# USV-BG-001-SP-A.net
KiCad netlist of a schematic drawn in EAGLE
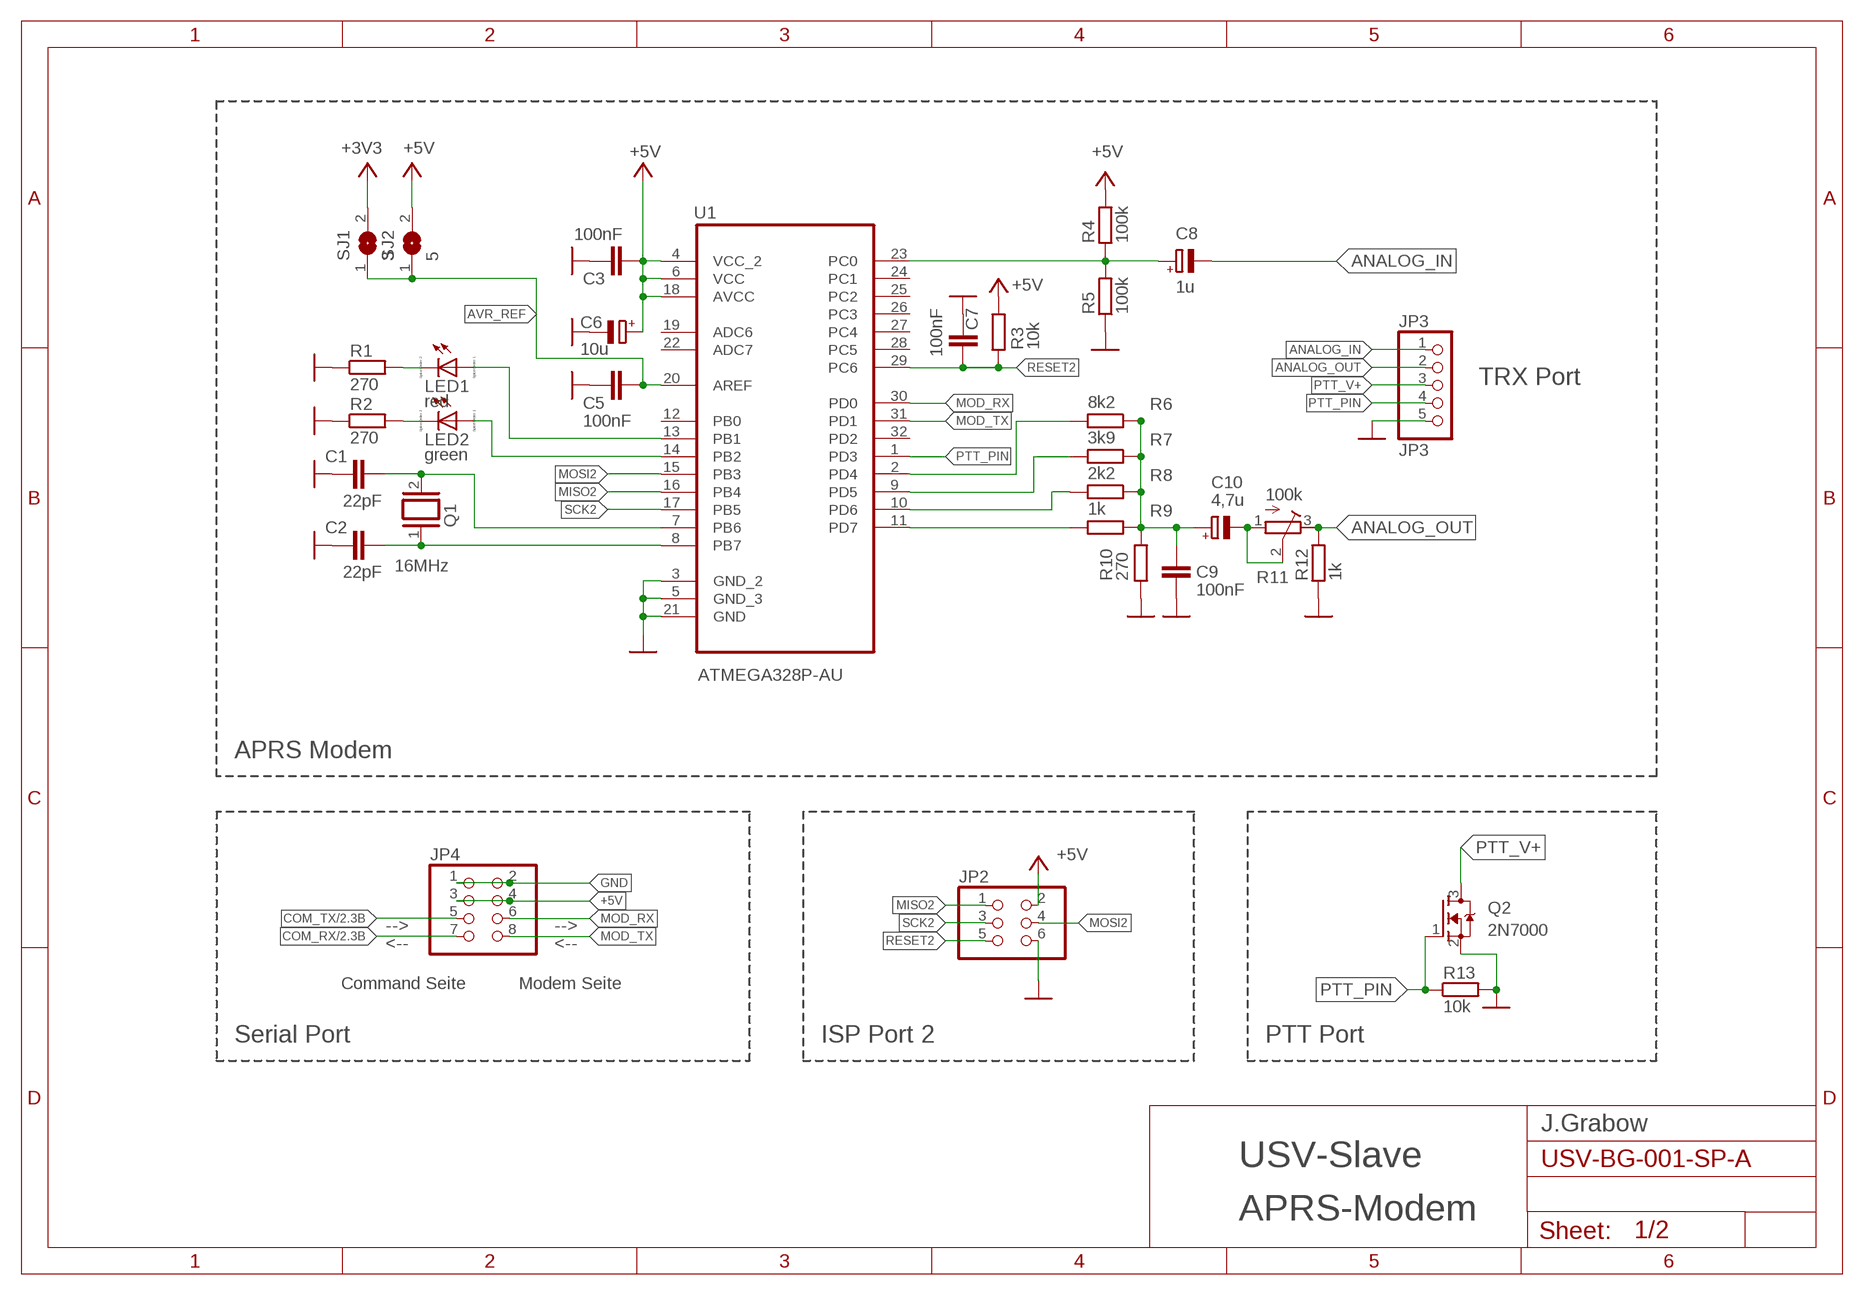
[diagram p0: schematic, sheet 1]
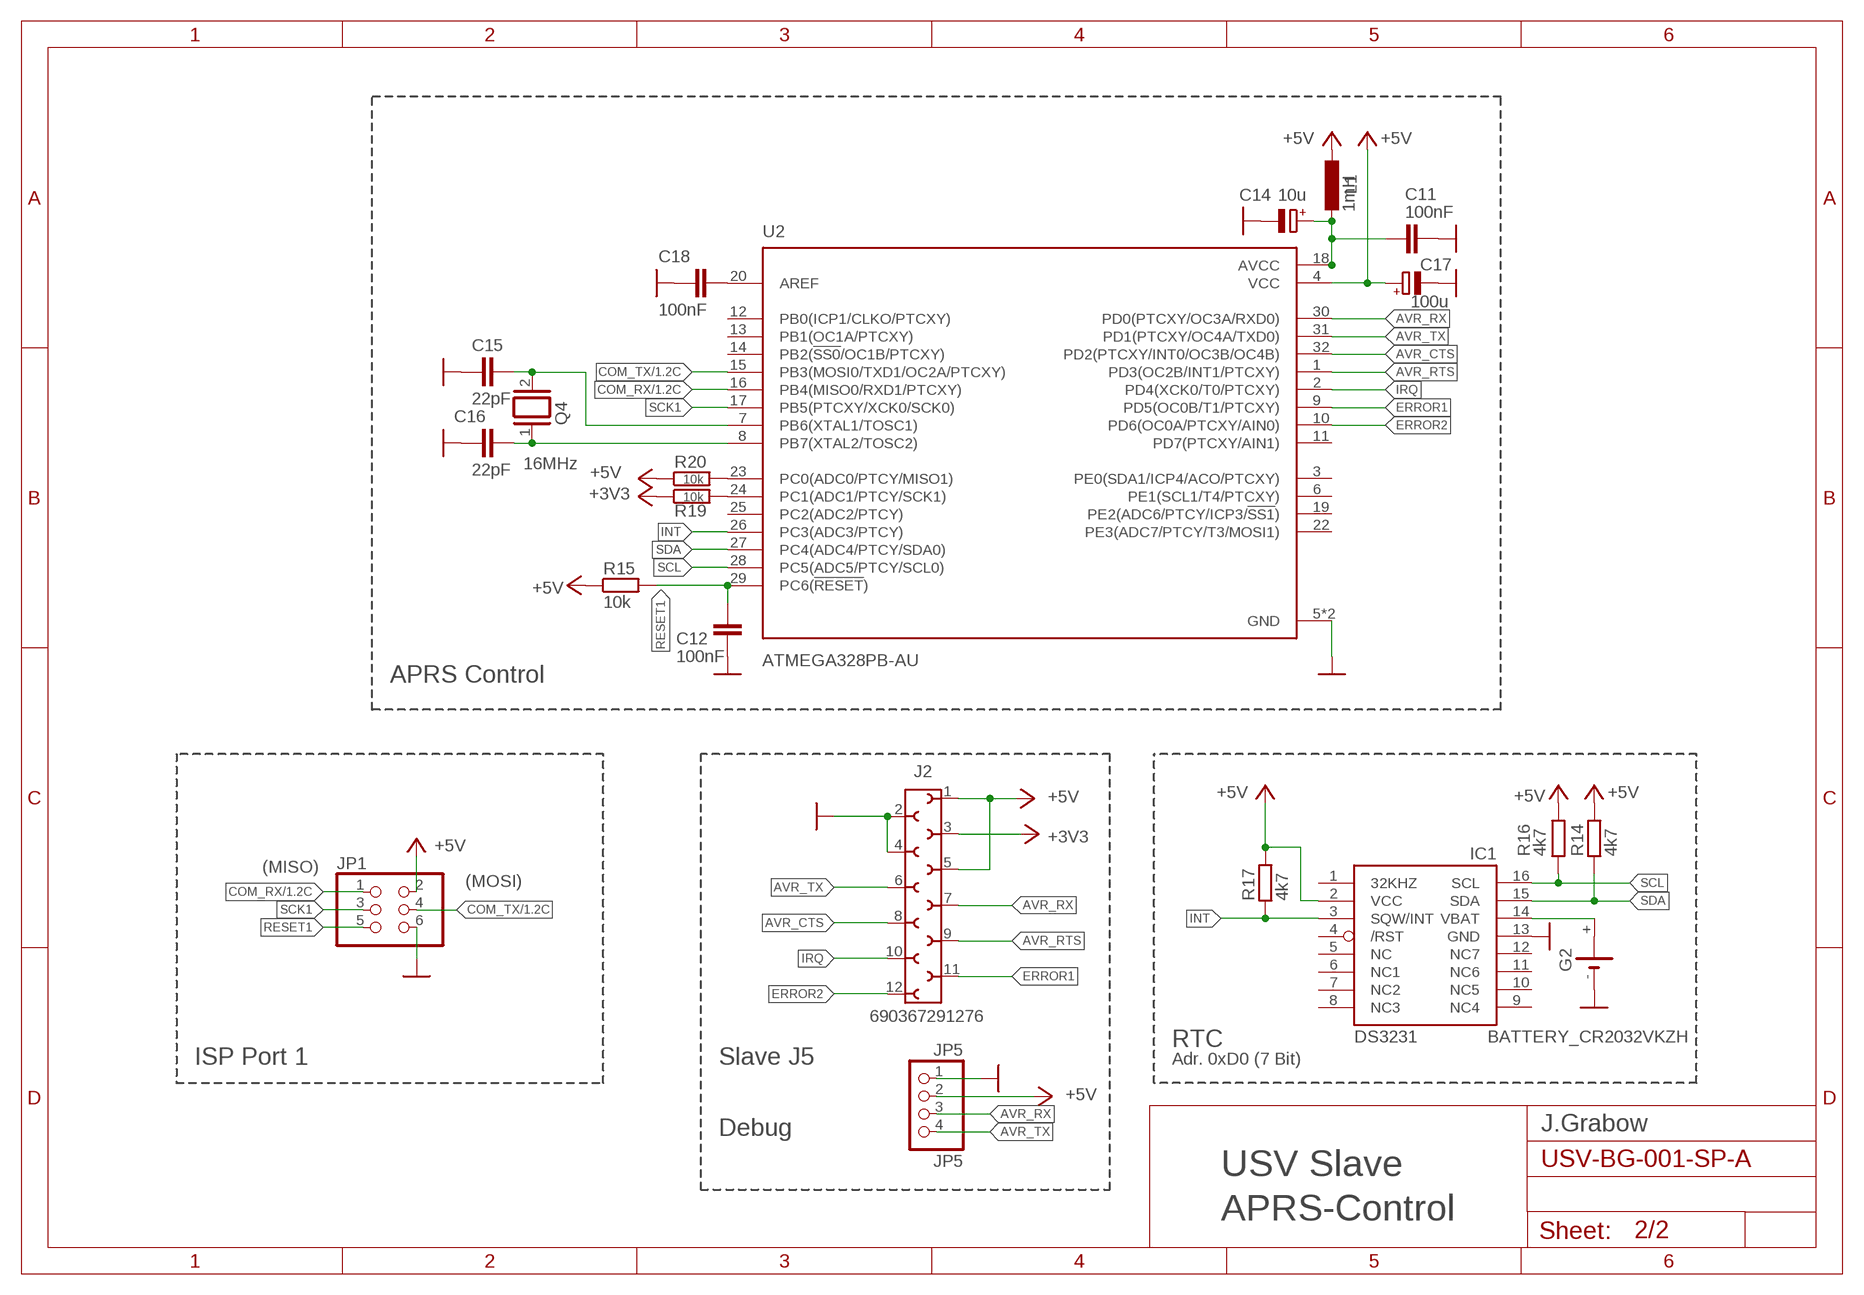
[diagram p1: schematic, sheet 2]

(export (version "E")
  (design (tool "Eeschema 10.0.6"))
  (components
    (comp (ref "C11")
      (value "100nF")
      (footprint "eagle-import:C0805")
      (libsource (lib "eagle-import") (part "C-EUC0805"))
    )
    (comp (ref "C12")
      (value "100nF")
      (footprint "eagle-import:C0805")
      (libsource (lib "eagle-import") (part "C-EUC0805"))
    )
    (comp (ref "C14")
      (value "10u")
      (footprint "eagle-import:SMC_B")
      (libsource (lib "eagle-import") (part "CPOL-EUSMCB"))
    )
    (comp (ref "C15")
      (value "22pF")
      (footprint "eagle-import:C0805")
      (libsource (lib "eagle-import") (part "C-EUC0805"))
    )
    (comp (ref "C16")
      (value "22pF")
      (footprint "eagle-import:C0805")
      (libsource (lib "eagle-import") (part "C-EUC0805"))
    )
    (comp (ref "C17")
      (value "100u")
      (footprint "eagle-import:SMC_B")
      (libsource (lib "eagle-import") (part "CPOL-EUSMCB"))
    )
    (comp (ref "C18")
      (value "100nF")
      (footprint "eagle-import:C0805")
      (libsource (lib "eagle-import") (part "C-EUC0805"))
    )
    (comp (ref "G2")
      (value "BATTERY_CR2032VKZH")
      (footprint "eagle-import:BATTERY_KZH20PCB-V")
      (libsource (lib "eagle-import") (part "BATTERY_CR2032VKZH"))
    )
    (comp (ref "IC1")
      (value "DS3231/SO")
      (footprint "eagle-import:SO16W")
      (fields (field (name "MF") "Maxim Integrated") (field (name "MP") "DS3231"))
      (libsource (lib "eagle-import") (part "DS3231/SO"))
    )
    (comp (ref "J2")
      (value "690367291276")
      (footprint "eagle-import:690367291276")
      (libsource (lib "eagle-import") (part "690367291276"))
    )
    (comp (ref "JP1")
      (value "PINHD-2X3")
      (footprint "eagle-import:2X03")
      (libsource (lib "eagle-import") (part "PINHD-2X3"))
    )
    (comp (ref "JP5")
      (value "JP5")
      (footprint "eagle-import:1X04")
      (libsource (lib "eagle-import") (part "PINHD-1X4"))
    )
    (comp (ref "L1")
      (value "1mH")
      (footprint "eagle-import:L1812")
      (libsource (lib "eagle-import") (part "L-EUL1812"))
    )
    (comp (ref "Q4")
      (value "16MHz")
      (footprint "eagle-import:QS")
      (libsource (lib "eagle-import") (part "XTAL/S"))
    )
    (comp (ref "R14")
      (value "4k7")
      (footprint "eagle-import:R0805")
      (libsource (lib "eagle-import") (part "R-EU_R0805"))
    )
    (comp (ref "R15")
      (value "10k")
      (footprint "eagle-import:R0805")
      (libsource (lib "eagle-import") (part "R-EU_R0805"))
    )
    (comp (ref "R16")
      (value "4k7")
      (footprint "eagle-import:R0805")
      (libsource (lib "eagle-import") (part "R-EU_R0805"))
    )
    (comp (ref "R17")
      (value "4k7")
      (footprint "eagle-import:R0805")
      (libsource (lib "eagle-import") (part "R-EU_R0805"))
    )
    (comp (ref "R19")
      (value "10k")
      (footprint "eagle-import:R0805")
      (libsource (lib "eagle-import") (part "R-EU_R0805"))
    )
    (comp (ref "R20")
      (value "10k")
      (footprint "eagle-import:R0805")
      (libsource (lib "eagle-import") (part "R-EU_R0805"))
    )
    (comp (ref "U2")
      (value "ATMEGA328PB-AU")
      (footprint "eagle-import:QFP80P900X900X120-32N")
      (fields (field (name "MF") "Microchip Technology"))
      (libsource (lib "eagle-import") (part "ATMEGA328PB-AU"))
    )
    (comp (ref "C1")
      (value "22pF")
      (footprint "eagle-import:C0805")
      (libsource (lib "eagle-import") (part "C-EUC0805"))
    )
    (comp (ref "C2")
      (value "22pF")
      (footprint "eagle-import:C0805")
      (libsource (lib "eagle-import") (part "C-EUC0805"))
    )
    (comp (ref "C3")
      (value "100nF")
      (footprint "eagle-import:C0805")
      (libsource (lib "eagle-import") (part "C-EUC0805"))
    )
    (comp (ref "C5")
      (value "100nF")
      (footprint "eagle-import:C0805")
      (libsource (lib "eagle-import") (part "C-EUC0805"))
    )
    (comp (ref "C6")
      (value "10u")
      (footprint "eagle-import:SMC_B")
      (libsource (lib "eagle-import") (part "CPOL-EUSMCB"))
    )
    (comp (ref "C7")
      (value "100nF")
      (footprint "eagle-import:C0805")
      (libsource (lib "eagle-import") (part "C-EUC0805"))
    )
    (comp (ref "C8")
      (value "1u")
      (footprint "eagle-import:SMC_B")
      (libsource (lib "eagle-import") (part "CPOL-EUSMCB"))
    )
    (comp (ref "C9")
      (value "100nF")
      (footprint "eagle-import:C0805")
      (libsource (lib "eagle-import") (part "C-EUC0805"))
    )
    (comp (ref "C10")
      (value "4,7u")
      (footprint "eagle-import:SMC_B")
      (libsource (lib "eagle-import") (part "CPOL-EUSMCB"))
    )
    (comp (ref "JP2")
      (value "PINHD-2X3")
      (footprint "eagle-import:2X03")
      (libsource (lib "eagle-import") (part "PINHD-2X3"))
    )
    (comp (ref "JP3")
      (value "JP3")
      (footprint "eagle-import:1X05")
      (libsource (lib "eagle-import") (part "PINHD-1X5"))
    )
    (comp (ref "JP4")
      (value "PINHD-2X4")
      (footprint "eagle-import:2X04")
      (libsource (lib "eagle-import") (part "PINHD-2X4"))
    )
    (comp (ref "LED1")
      (value "red")
      (footprint "eagle-import:LED_1206")
      (libsource (lib "eagle-import") (part "LED_E"))
    )
    (comp (ref "LED2")
      (value "green")
      (footprint "eagle-import:LED_1206")
      (libsource (lib "eagle-import") (part "LED_E"))
    )
    (comp (ref "Q1")
      (value "16MHz")
      (footprint "eagle-import:QS")
      (libsource (lib "eagle-import") (part "XTAL/S"))
    )
    (comp (ref "Q2")
      (value "2N7000")
      (footprint "eagle-import:SOT23")
      (libsource (lib "eagle-import") (part "MOSFET-NREFLOW"))
    )
    (comp (ref "R1")
      (value "270")
      (footprint "eagle-import:R0805")
      (libsource (lib "eagle-import") (part "R-EU_R0805"))
    )
    (comp (ref "R2")
      (value "270")
      (footprint "eagle-import:R0805")
      (libsource (lib "eagle-import") (part "R-EU_R0805"))
    )
    (comp (ref "R3")
      (value "10k")
      (footprint "eagle-import:R0805")
      (libsource (lib "eagle-import") (part "R-EU_R0805"))
    )
    (comp (ref "R4")
      (value "100k")
      (footprint "eagle-import:R0805")
      (libsource (lib "eagle-import") (part "R-EU_R0805"))
    )
    (comp (ref "R5")
      (value "100k")
      (footprint "eagle-import:R0805")
      (libsource (lib "eagle-import") (part "R-EU_R0805"))
    )
    (comp (ref "R6")
      (value "8k2")
      (footprint "eagle-import:R0805")
      (libsource (lib "eagle-import") (part "R-EU_R0805"))
    )
    (comp (ref "R7")
      (value "3k9")
      (footprint "eagle-import:R0805")
      (libsource (lib "eagle-import") (part "R-EU_R0805"))
    )
    (comp (ref "R8")
      (value "2k2")
      (footprint "eagle-import:R0805")
      (libsource (lib "eagle-import") (part "R-EU_R0805"))
    )
    (comp (ref "R9")
      (value "1k")
      (footprint "eagle-import:R0805")
      (libsource (lib "eagle-import") (part "R-EU_R0805"))
    )
    (comp (ref "R10")
      (value "270")
      (footprint "eagle-import:R0805")
      (libsource (lib "eagle-import") (part "R-EU_R0805"))
    )
    (comp (ref "R11")
      (value "100k")
      (footprint "eagle-import:RTRIM3339P")
      (libsource (lib "eagle-import") (part "R-TRIMM3339P"))
    )
    (comp (ref "R12")
      (value "1k")
      (footprint "eagle-import:R0805")
      (libsource (lib "eagle-import") (part "R-EU_R0805"))
    )
    (comp (ref "R13")
      (value "10k")
      (footprint "eagle-import:R0805")
      (libsource (lib "eagle-import") (part "R-EU_R0805"))
    )
    (comp (ref "SJ1") (value "3") (footprint "eagle-import:SJ") (libsource (lib "eagle-import") (part "SJ")))
    (comp (ref "SJ2") (value "5") (footprint "eagle-import:SJ") (libsource (lib "eagle-import") (part "SJ")))
    (comp (ref "U1")
      (value "ATMEGA328P-AU")
      (footprint "eagle-import:QFP80P900X900X120-32N")
      (libsource (lib "eagle-import") (part "ATMEGA328P-AU"))
    )
  )
  (nets
    (net (code "1") (name "+3V3") (class "Default")
      (node (ref "J2") (pin "3") (pinfunction "3_3") (pintype "passive"))
      (node (ref "R19") (pin "1") (pinfunction "1_1") (pintype "passive"))
      (node (ref "SJ1") (pin "2") (pinfunction "2_2") (pintype "passive"))
    )
    (net (code "2") (name "+5V") (class "Default")
      (node (ref "C17") (pin "+") (pinfunction "+_+") (pintype "passive"))
      (node (ref "C3") (pin "2") (pinfunction "2_2") (pintype "passive"))
      (node (ref "C6") (pin "+") (pinfunction "+_+") (pintype "passive"))
      (node (ref "IC1") (pin "2") (pinfunction "VCC_2") (pintype "power_in"))
      (node (ref "J2") (pin "1") (pinfunction "1_1") (pintype "passive"))
      (node (ref "J2") (pin "5") (pinfunction "5_5") (pintype "passive"))
      (node (ref "JP1") (pin "2") (pinfunction "2_2") (pintype "passive"))
      (node (ref "JP2") (pin "2") (pinfunction "2_2") (pintype "passive"))
      (node (ref "JP4") (pin "3") (pinfunction "3_3") (pintype "passive"))
      (node (ref "JP4") (pin "4") (pinfunction "4_4") (pintype "passive"))
      (node (ref "JP5") (pin "2") (pinfunction "2_2") (pintype "passive"))
      (node (ref "L1") (pin "1") (pinfunction "1_1") (pintype "passive"))
      (node (ref "R14") (pin "2") (pinfunction "2_2") (pintype "passive"))
      (node (ref "R15") (pin "1") (pinfunction "1_1") (pintype "passive"))
      (node (ref "R16") (pin "2") (pinfunction "2_2") (pintype "passive"))
      (node (ref "R17") (pin "2") (pinfunction "2_2") (pintype "passive"))
      (node (ref "R20") (pin "1") (pinfunction "1_1") (pintype "passive"))
      (node (ref "R3") (pin "1") (pinfunction "1_1") (pintype "passive"))
      (node (ref "R4") (pin "2") (pinfunction "2_2") (pintype "passive"))
      (node (ref "SJ2") (pin "2") (pinfunction "2_2") (pintype "passive"))
      (node (ref "U1") (pin "18") (pinfunction "AVCC_18") (pintype "power_in"))
      (node (ref "U1") (pin "4") (pinfunction "VCC_2_4") (pintype "power_in"))
      (node (ref "U1") (pin "6") (pinfunction "VCC_6") (pintype "power_in"))
      (node (ref "U2") (pin "4") (pinfunction "VCC_4") (pintype "power_in"))
    )
    (net (code "3") (name "ANALOG_IN") (class "Default")
      (node (ref "C8") (pin "-") (pinfunction "-_-") (pintype "passive"))
      (node (ref "JP3") (pin "1") (pinfunction "1_1") (pintype "passive"))
    )
    (net (code "4") (name "ANALOG_OUT") (class "Default")
      (node (ref "JP3") (pin "2") (pinfunction "2_2") (pintype "passive"))
      (node (ref "R11") (pin "3") (pinfunction "E_3") (pintype "passive"))
      (node (ref "R12") (pin "2") (pinfunction "2_2") (pintype "passive"))
    )
    (net (code "5") (name "AVR_CTS") (class "Default")
      (node (ref "J2") (pin "8") (pinfunction "8_8") (pintype "passive"))
      (node (ref "U2") (pin "32") (pinfunction "PD2(PTCXY/INT0/OC3B/OC4B)_32") (pintype "bidirectional"))
    )
    (net (code "6") (name "AVR_REF") (class "Default")
      (node (ref "C5") (pin "2") (pinfunction "2_2") (pintype "passive"))
      (node (ref "SJ1") (pin "1") (pinfunction "1_1") (pintype "passive"))
      (node (ref "SJ2") (pin "1") (pinfunction "1_1") (pintype "passive"))
      (node (ref "U1") (pin "20") (pinfunction "AREF_20") (pintype "input"))
    )
    (net (code "7") (name "AVR_RTS") (class "Default")
      (node (ref "J2") (pin "9") (pinfunction "9_9") (pintype "passive"))
      (node (ref "U2") (pin "1") (pinfunction "PD3(OC2B/INT1/PTCXY)_1") (pintype "bidirectional"))
    )
    (net (code "8") (name "AVR_RX") (class "Default")
      (node (ref "J2") (pin "7") (pinfunction "7_7") (pintype "passive"))
      (node (ref "JP5") (pin "3") (pinfunction "3_3") (pintype "passive"))
      (node (ref "U2") (pin "30") (pinfunction "PD0(PTCXY/OC3A/RXD0)_30") (pintype "bidirectional"))
    )
    (net (code "9") (name "AVR_TX") (class "Default")
      (node (ref "J2") (pin "6") (pinfunction "6_6") (pintype "passive"))
      (node (ref "JP5") (pin "4") (pinfunction "4_4") (pintype "passive"))
      (node (ref "U2") (pin "31") (pinfunction "PD1(PTCXY/OC4A/TXD0)_31") (pintype "bidirectional"))
    )
    (net (code "10") (name "COM_RX") (class "Default")
      (node (ref "JP1") (pin "1") (pinfunction "1_1") (pintype "passive"))
      (node (ref "JP4") (pin "7") (pinfunction "7_7") (pintype "passive"))
      (node (ref "U2") (pin "16") (pinfunction "PB4(MISO0/RXD1/PTCXY)_16") (pintype "bidirectional"))
    )
    (net (code "11") (name "COM_TX") (class "Default")
      (node (ref "JP1") (pin "4") (pinfunction "4_4") (pintype "passive"))
      (node (ref "JP4") (pin "5") (pinfunction "5_5") (pintype "passive"))
      (node (ref "U2") (pin "15") (pinfunction "PB3(MOSI0/TXD1/OC2A/PTCXY)_15") (pintype "bidirectional"))
    )
    (net (code "12") (name "ERROR1") (class "Default")
      (node (ref "J2") (pin "11") (pinfunction "11_11") (pintype "passive"))
      (node (ref "U2") (pin "9") (pinfunction "PD5(OC0B/T1/PTCXY)_9") (pintype "bidirectional"))
    )
    (net (code "13") (name "ERROR2") (class "Default")
      (node (ref "J2") (pin "12") (pinfunction "12_12") (pintype "passive"))
      (node (ref "U2") (pin "10") (pinfunction "PD6(OC0A/PTCXY/AIN0)_10") (pintype "bidirectional"))
    )
    (net (code "14") (name "GND") (class "Default")
      (node (ref "C1") (pin "2") (pinfunction "2_2") (pintype "passive"))
      (node (ref "C11") (pin "2") (pinfunction "2_2") (pintype "passive"))
      (node (ref "C12") (pin "2") (pinfunction "2_2") (pintype "passive"))
      (node (ref "C14") (pin "-") (pinfunction "-_-") (pintype "passive"))
      (node (ref "C15") (pin "2") (pinfunction "2_2") (pintype "passive"))
      (node (ref "C16") (pin "2") (pinfunction "2_2") (pintype "passive"))
      (node (ref "C17") (pin "-") (pinfunction "-_-") (pintype "passive"))
      (node (ref "C18") (pin "1") (pinfunction "1_1") (pintype "passive"))
      (node (ref "C2") (pin "2") (pinfunction "2_2") (pintype "passive"))
      (node (ref "C3") (pin "1") (pinfunction "1_1") (pintype "passive"))
      (node (ref "C5") (pin "1") (pinfunction "1_1") (pintype "passive"))
      (node (ref "C6") (pin "-") (pinfunction "-_-") (pintype "passive"))
      (node (ref "C7") (pin "1") (pinfunction "1_1") (pintype "passive"))
      (node (ref "C9") (pin "2") (pinfunction "2_2") (pintype "passive"))
      (node (ref "G2") (pin "-") (pinfunction "-_-") (pintype "passive"))
      (node (ref "IC1") (pin "13") (pinfunction "GND_13") (pintype "power_in"))
      (node (ref "J2") (pin "2") (pinfunction "2_2") (pintype "passive"))
      (node (ref "J2") (pin "4") (pinfunction "4_4") (pintype "passive"))
      (node (ref "JP1") (pin "6") (pinfunction "6_6") (pintype "passive"))
      (node (ref "JP2") (pin "6") (pinfunction "6_6") (pintype "passive"))
      (node (ref "JP3") (pin "5") (pinfunction "5_5") (pintype "passive"))
      (node (ref "JP4") (pin "1") (pinfunction "1_1") (pintype "passive"))
      (node (ref "JP4") (pin "2") (pinfunction "2_2") (pintype "passive"))
      (node (ref "JP5") (pin "1") (pinfunction "1_1") (pintype "passive"))
      (node (ref "Q2") (pin "2") (pinfunction "S_2") (pintype "bidirectional"))
      (node (ref "R1") (pin "1") (pinfunction "1_1") (pintype "passive"))
      (node (ref "R10") (pin "1") (pinfunction "1_1") (pintype "passive"))
      (node (ref "R12") (pin "1") (pinfunction "1_1") (pintype "passive"))
      (node (ref "R13") (pin "2") (pinfunction "2_2") (pintype "passive"))
      (node (ref "R2") (pin "1") (pinfunction "1_1") (pintype "passive"))
      (node (ref "R5") (pin "1") (pinfunction "1_1") (pintype "passive"))
      (node (ref "U1") (pin "21") (pinfunction "GND_21") (pintype "passive"))
      (node (ref "U1") (pin "3") (pinfunction "GND_2_3") (pintype "passive"))
      (node (ref "U1") (pin "5") (pinfunction "GND_3_5") (pintype "passive"))
      (node (ref "U2") (pin "21") (pinfunction "GND_21") (pintype "power_in"))
      (node (ref "U2") (pin "5") (pinfunction "GND_5") (pintype "power_in"))
    )
    (net (code "15") (name "INT") (class "Default")
      (node (ref "IC1") (pin "3") (pinfunction "SQW/INT_3") (pintype "output"))
      (node (ref "R17") (pin "1") (pinfunction "1_1") (pintype "passive"))
      (node (ref "U2") (pin "26") (pinfunction "PC3(ADC3/PTCY)_26") (pintype "bidirectional"))
    )
    (net (code "16") (name "IRQ") (class "Default")
      (node (ref "J2") (pin "10") (pinfunction "10_10") (pintype "passive"))
      (node (ref "U2") (pin "2") (pinfunction "PD4(XCK0/T0/PTCXY)_2") (pintype "bidirectional"))
    )
    (net (code "17") (name "MISO2") (class "Default")
      (node (ref "JP2") (pin "1") (pinfunction "1_1") (pintype "passive"))
      (node (ref "U1") (pin "16") (pinfunction "PB4_16") (pintype "bidirectional"))
    )
    (net (code "18") (name "MOD_RX") (class "Default")
      (node (ref "JP4") (pin "6") (pinfunction "6_6") (pintype "passive"))
      (node (ref "U1") (pin "30") (pinfunction "PD0_30") (pintype "bidirectional"))
    )
    (net (code "19") (name "MOD_TX") (class "Default")
      (node (ref "JP4") (pin "8") (pinfunction "8_8") (pintype "passive"))
      (node (ref "U1") (pin "31") (pinfunction "PD1_31") (pintype "bidirectional"))
    )
    (net (code "20") (name "MOSI2") (class "Default")
      (node (ref "JP2") (pin "4") (pinfunction "4_4") (pintype "passive"))
      (node (ref "U1") (pin "15") (pinfunction "PB3_15") (pintype "bidirectional"))
    )
    (net (code "21") (name "Net-(C10-Pad+)") (class "Default")
      (node (ref "C10") (pin "+") (pinfunction "+_+") (pintype "passive"))
      (node (ref "C9") (pin "1") (pinfunction "1_1") (pintype "passive"))
      (node (ref "R10") (pin "2") (pinfunction "2_2") (pintype "passive"))
      (node (ref "R6") (pin "1") (pinfunction "1_1") (pintype "passive"))
      (node (ref "R7") (pin "1") (pinfunction "1_1") (pintype "passive"))
      (node (ref "R8") (pin "1") (pinfunction "1_1") (pintype "passive"))
      (node (ref "R9") (pin "1") (pinfunction "1_1") (pintype "passive"))
    )
    (net (code "22") (name "Net-(IC1-VBAT)") (class "Default")
      (node (ref "G2") (pin "+") (pinfunction "+_+") (pintype "passive"))
      (node (ref "IC1") (pin "14") (pinfunction "VBAT_14") (pintype "power_in"))
    )
    (net (code "23") (name "Net-(LED1-PadC)") (class "Default")
      (node (ref "LED1") (pin "C") (pinfunction "C_C") (pintype "passive"))
      (node (ref "R1") (pin "2") (pinfunction "2_2") (pintype "passive"))
    )
    (net (code "24") (name "Net-(LED2-PadC)") (class "Default")
      (node (ref "LED2") (pin "C") (pinfunction "C_C") (pintype "passive"))
      (node (ref "R2") (pin "2") (pinfunction "2_2") (pintype "passive"))
    )
    (net (code "25") (name "Net-(R11-A)") (class "Default")
      (node (ref "C10") (pin "-") (pinfunction "-_-") (pintype "passive"))
      (node (ref "R11") (pin "1") (pinfunction "A_1") (pintype "passive"))
      (node (ref "R11") (pin "2") (pinfunction "S_2") (pintype "passive"))
    )
    (net (code "26") (name "Net-(U1-PB1)") (class "Default")
      (node (ref "LED1") (pin "A") (pinfunction "A_A") (pintype "passive"))
      (node (ref "U1") (pin "13") (pinfunction "PB1_13") (pintype "bidirectional"))
    )
    (net (code "27") (name "Net-(U1-PB2)") (class "Default")
      (node (ref "LED2") (pin "A") (pinfunction "A_A") (pintype "passive"))
      (node (ref "U1") (pin "14") (pinfunction "PB2_14") (pintype "bidirectional"))
    )
    (net (code "28") (name "Net-(U1-PB6)") (class "Default")
      (node (ref "C1") (pin "1") (pinfunction "1_1") (pintype "passive"))
      (node (ref "Q1") (pin "2") (pinfunction "2_2") (pintype "passive"))
      (node (ref "U1") (pin "7") (pinfunction "PB6_7") (pintype "bidirectional"))
    )
    (net (code "29") (name "Net-(U1-PB7)") (class "Default")
      (node (ref "C2") (pin "1") (pinfunction "1_1") (pintype "passive"))
      (node (ref "Q1") (pin "1") (pinfunction "1_1") (pintype "passive"))
      (node (ref "U1") (pin "8") (pinfunction "PB7_8") (pintype "bidirectional"))
    )
    (net (code "30") (name "Net-(U1-PC0)") (class "Default")
      (node (ref "C8") (pin "+") (pinfunction "+_+") (pintype "passive"))
      (node (ref "R4") (pin "1") (pinfunction "1_1") (pintype "passive"))
      (node (ref "R5") (pin "2") (pinfunction "2_2") (pintype "passive"))
      (node (ref "U1") (pin "23") (pinfunction "PC0_23") (pintype "bidirectional"))
    )
    (net (code "31") (name "Net-(U1-PD4)") (class "Default")
      (node (ref "R6") (pin "2") (pinfunction "2_2") (pintype "passive"))
      (node (ref "U1") (pin "2") (pinfunction "PD4_2") (pintype "bidirectional"))
    )
    (net (code "32") (name "Net-(U1-PD5)") (class "Default")
      (node (ref "R7") (pin "2") (pinfunction "2_2") (pintype "passive"))
      (node (ref "U1") (pin "9") (pinfunction "PD5_9") (pintype "bidirectional"))
    )
    (net (code "33") (name "Net-(U1-PD6)") (class "Default")
      (node (ref "R8") (pin "2") (pinfunction "2_2") (pintype "passive"))
      (node (ref "U1") (pin "10") (pinfunction "PD6_10") (pintype "bidirectional"))
    )
    (net (code "34") (name "Net-(U1-PD7)") (class "Default")
      (node (ref "R9") (pin "2") (pinfunction "2_2") (pintype "passive"))
      (node (ref "U1") (pin "11") (pinfunction "PD7_11") (pintype "bidirectional"))
    )
    (net (code "35") (name "Net-(U2-AREF)") (class "Default")
      (node (ref "C18") (pin "2") (pinfunction "2_2") (pintype "passive"))
      (node (ref "U2") (pin "20") (pinfunction "AREF_20") (pintype "input"))
    )
    (net (code "36") (name "Net-(U2-AVCC)") (class "Default")
      (node (ref "C11") (pin "1") (pinfunction "1_1") (pintype "passive"))
      (node (ref "C14") (pin "+") (pinfunction "+_+") (pintype "passive"))
      (node (ref "L1") (pin "2") (pinfunction "2_2") (pintype "passive"))
      (node (ref "U2") (pin "18") (pinfunction "AVCC_18") (pintype "power_in"))
    )
    (net (code "37") (name "Net-(U2-PB6(XTAL1{slash}TOSC1))") (class "Default")
      (node (ref "C15") (pin "1") (pinfunction "1_1") (pintype "passive"))
      (node (ref "Q4") (pin "2") (pinfunction "2_2") (pintype "passive"))
      (node (ref "U2") (pin "7") (pinfunction "PB6(XTAL1/TOSC1)_7") (pintype "bidirectional"))
    )
    (net (code "38") (name "Net-(U2-PB7(XTAL2{slash}TOSC2))") (class "Default")
      (node (ref "C16") (pin "1") (pinfunction "1_1") (pintype "passive"))
      (node (ref "Q4") (pin "1") (pinfunction "1_1") (pintype "passive"))
      (node (ref "U2") (pin "8") (pinfunction "PB7(XTAL2/TOSC2)_8") (pintype "bidirectional"))
    )
    (net (code "39") (name "Net-(U2-PC0(ADC0{slash}PTCY{slash}MISO1))") (class "Default")
      (node (ref "R20") (pin "2") (pinfunction "2_2") (pintype "passive"))
      (node (ref "U2") (pin "23") (pinfunction "PC0(ADC0/PTCY/MISO1)_23") (pintype "bidirectional"))
    )
    (net (code "40") (name "Net-(U2-PC1(ADC1{slash}PTCY{slash}SCK1))") (class "Default")
      (node (ref "R19") (pin "2") (pinfunction "2_2") (pintype "passive"))
      (node (ref "U2") (pin "24") (pinfunction "PC1(ADC1/PTCY/SCK1)_24") (pintype "bidirectional"))
    )
    (net (code "41") (name "PTT_PIN") (class "Default")
      (node (ref "JP3") (pin "4") (pinfunction "4_4") (pintype "passive"))
      (node (ref "Q2") (pin "1") (pinfunction "G_1") (pintype "bidirectional"))
      (node (ref "R13") (pin "1") (pinfunction "1_1") (pintype "passive"))
      (node (ref "U1") (pin "1") (pinfunction "PD3_1") (pintype "bidirectional"))
    )
    (net (code "42") (name "PTT_V+") (class "Default")
      (node (ref "JP3") (pin "3") (pinfunction "3_3") (pintype "passive"))
      (node (ref "Q2") (pin "3") (pinfunction "D_3") (pintype "bidirectional"))
    )
    (net (code "43") (name "RESET1") (class "Default")
      (node (ref "C12") (pin "1") (pinfunction "1_1") (pintype "passive"))
      (node (ref "JP1") (pin "5") (pinfunction "5_5") (pintype "passive"))
      (node (ref "R15") (pin "2") (pinfunction "2_2") (pintype "passive"))
      (node (ref "U2") (pin "29") (pinfunction "PC6(~{RESET})_29") (pintype "bidirectional"))
    )
    (net (code "44") (name "RESET2") (class "Default")
      (node (ref "C7") (pin "2") (pinfunction "2_2") (pintype "passive"))
      (node (ref "JP2") (pin "5") (pinfunction "5_5") (pintype "passive"))
      (node (ref "R3") (pin "2") (pinfunction "2_2") (pintype "passive"))
      (node (ref "U1") (pin "29") (pinfunction "PC6_29") (pintype "bidirectional"))
    )
    (net (code "45") (name "SCK1") (class "Default")
      (node (ref "JP1") (pin "3") (pinfunction "3_3") (pintype "passive"))
      (node (ref "U2") (pin "17") (pinfunction "PB5(PTCXY/XCK0/SCK0)_17") (pintype "bidirectional"))
    )
    (net (code "46") (name "SCK2") (class "Default")
      (node (ref "JP2") (pin "3") (pinfunction "3_3") (pintype "passive"))
      (node (ref "U1") (pin "17") (pinfunction "PB5_17") (pintype "bidirectional"))
    )
    (net (code "47") (name "SCL") (class "Default")
      (node (ref "IC1") (pin "16") (pinfunction "SCL_16") (pintype "bidirectional"))
      (node (ref "R16") (pin "1") (pinfunction "1_1") (pintype "passive"))
      (node (ref "U2") (pin "28") (pinfunction "PC5(ADC5/PTCY/SCL0)_28") (pintype "bidirectional"))
    )
    (net (code "48") (name "SDA") (class "Default")
      (node (ref "IC1") (pin "15") (pinfunction "SDA_15") (pintype "bidirectional"))
      (node (ref "R14") (pin "1") (pinfunction "1_1") (pintype "passive"))
      (node (ref "U2") (pin "27") (pinfunction "PC4(ADC4/PTCY/SDA0)_27") (pintype "bidirectional"))
    )
    (net (code "49") (name "unconnected-(G2-+-Pad+@1)") (class "Default")
      (node (ref "G2") (pin "+@1") (pinfunction "+_+@1") (pintype "passive"))
    )
    (net (code "50") (name "unconnected-(IC1-32KHZ-Pad1)") (class "Default")
      (node (ref "IC1") (pin "1") (pinfunction "32KHZ_1") (pintype "output"))
    )
    (net (code "51") (name "unconnected-(IC1-NC-Pad5)") (class "Default")
      (node (ref "IC1") (pin "5") (pinfunction "NC_5") (pintype "no_connect"))
    )
    (net (code "52") (name "unconnected-(IC1-NC1-Pad6)") (class "Default")
      (node (ref "IC1") (pin "6") (pinfunction "NC1_6") (pintype "no_connect"))
    )
    (net (code "53") (name "unconnected-(IC1-NC2-Pad7)") (class "Default")
      (node (ref "IC1") (pin "7") (pinfunction "NC2_7") (pintype "no_connect"))
    )
    (net (code "54") (name "unconnected-(IC1-NC3-Pad8)") (class "Default")
      (node (ref "IC1") (pin "8") (pinfunction "NC3_8") (pintype "no_connect"))
    )
    (net (code "55") (name "unconnected-(IC1-NC4-Pad9)") (class "Default")
      (node (ref "IC1") (pin "9") (pinfunction "NC4_9") (pintype "no_connect"))
    )
    (net (code "56") (name "unconnected-(IC1-NC5-Pad10)") (class "Default")
      (node (ref "IC1") (pin "10") (pinfunction "NC5_10") (pintype "no_connect"))
    )
    (net (code "57") (name "unconnected-(IC1-NC6-Pad11)") (class "Default")
      (node (ref "IC1") (pin "11") (pinfunction "NC6_11") (pintype "no_connect"))
    )
    (net (code "58") (name "unconnected-(IC1-NC7-Pad12)") (class "Default")
      (node (ref "IC1") (pin "12") (pinfunction "NC7_12") (pintype "no_connect"))
    )
    (net (code "59") (name "unconnected-(IC1-{slash}RST-Pad4)") (class "Default")
      (node (ref "IC1") (pin "4") (pinfunction "/RST_4") (pintype "passive"))
    )
    (net (code "60") (name "unconnected-(U1-ADC6-Pad19)") (class "Default")
      (node (ref "U1") (pin "19") (pinfunction "ADC6_19") (pintype "input"))
    )
    (net (code "61") (name "unconnected-(U1-ADC7-Pad22)") (class "Default")
      (node (ref "U1") (pin "22") (pinfunction "ADC7_22") (pintype "input"))
    )
    (net (code "62") (name "unconnected-(U1-PB0-Pad12)") (class "Default")
      (node (ref "U1") (pin "12") (pinfunction "PB0_12") (pintype "bidirectional"))
    )
    (net (code "63") (name "unconnected-(U1-PC1-Pad24)") (class "Default")
      (node (ref "U1") (pin "24") (pinfunction "PC1_24") (pintype "bidirectional"))
    )
    (net (code "64") (name "unconnected-(U1-PC2-Pad25)") (class "Default")
      (node (ref "U1") (pin "25") (pinfunction "PC2_25") (pintype "bidirectional"))
    )
    (net (code "65") (name "unconnected-(U1-PC3-Pad26)") (class "Default")
      (node (ref "U1") (pin "26") (pinfunction "PC3_26") (pintype "bidirectional"))
    )
    (net (code "66") (name "unconnected-(U1-PC4-Pad27)") (class "Default")
      (node (ref "U1") (pin "27") (pinfunction "PC4_27") (pintype "bidirectional"))
    )
    (net (code "67") (name "unconnected-(U1-PC5-Pad28)") (class "Default")
      (node (ref "U1") (pin "28") (pinfunction "PC5_28") (pintype "bidirectional"))
    )
    (net (code "68") (name "unconnected-(U1-PD2-Pad32)") (class "Default")
      (node (ref "U1") (pin "32") (pinfunction "PD2_32") (pintype "bidirectional"))
    )
    (net (code "69") (name "unconnected-(U2-PB0(ICP1{slash}CLKO{slash}PTCXY)-Pad12)") (class "Default")
      (node (ref "U2") (pin "12") (pinfunction "PB0(ICP1/CLKO/PTCXY)_12") (pintype "bidirectional"))
    )
    (net (code "70") (name "unconnected-(U2-PB1(OC1A{slash}PTCXY)-Pad13)") (class "Default")
      (node (ref "U2") (pin "13") (pinfunction "PB1(OC1A/PTCXY)_13") (pintype "bidirectional"))
    )
    (net (code "71") (name "unconnected-(U2-PB2(~{SS0}{slash}OC1B{slash}PTCXY)-Pad14)") (class "Default")
      (node (ref "U2") (pin "14") (pinfunction "PB2(~{SS0}/OC1B/PTCXY)_14") (pintype "bidirectional"))
    )
    (net (code "72") (name "unconnected-(U2-PC2(ADC2{slash}PTCY)-Pad25)") (class "Default")
      (node (ref "U2") (pin "25") (pinfunction "PC2(ADC2/PTCY)_25") (pintype "bidirectional"))
    )
    (net (code "73") (name "unconnected-(U2-PD7(PTCXY{slash}AIN1)-Pad11)") (class "Default")
      (node (ref "U2") (pin "11") (pinfunction "PD7(PTCXY/AIN1)_11") (pintype "bidirectional"))
    )
    (net (code "74") (name "unconnected-(U2-PE0(SDA1{slash}ICP4{slash}ACO{slash}PTCXY)-Pad3)") (class "Default")
      (node (ref "U2") (pin "3") (pinfunction "PE0(SDA1/ICP4/ACO/PTCXY)_3") (pintype "bidirectional"))
    )
    (net (code "75") (name "unconnected-(U2-PE1(SCL1{slash}T4{slash}PTCXY)-Pad6)") (class "Default")
      (node (ref "U2") (pin "6") (pinfunction "PE1(SCL1/T4/PTCXY)_6") (pintype "bidirectional"))
    )
    (net (code "76") (name "unconnected-(U2-PE2(ADC6{slash}PTCY{slash}ICP3{slash}~{SS1})-Pad19)") (class "Default")
      (node (ref "U2") (pin "19") (pinfunction "PE2(ADC6/PTCY/ICP3/~{SS1})_19") (pintype "bidirectional"))
    )
    (net (code "77") (name "unconnected-(U2-PE3(ADC7{slash}PTCY{slash}T3{slash}MOSI1)-Pad22)") (class "Default")
      (node (ref "U2") (pin "22") (pinfunction "PE3(ADC7/PTCY/T3/MOSI1)_22") (pintype "bidirectional"))
    )
  )
)
